# MCU.net
KiCad netlist of a schematic drawn in Altium Designer
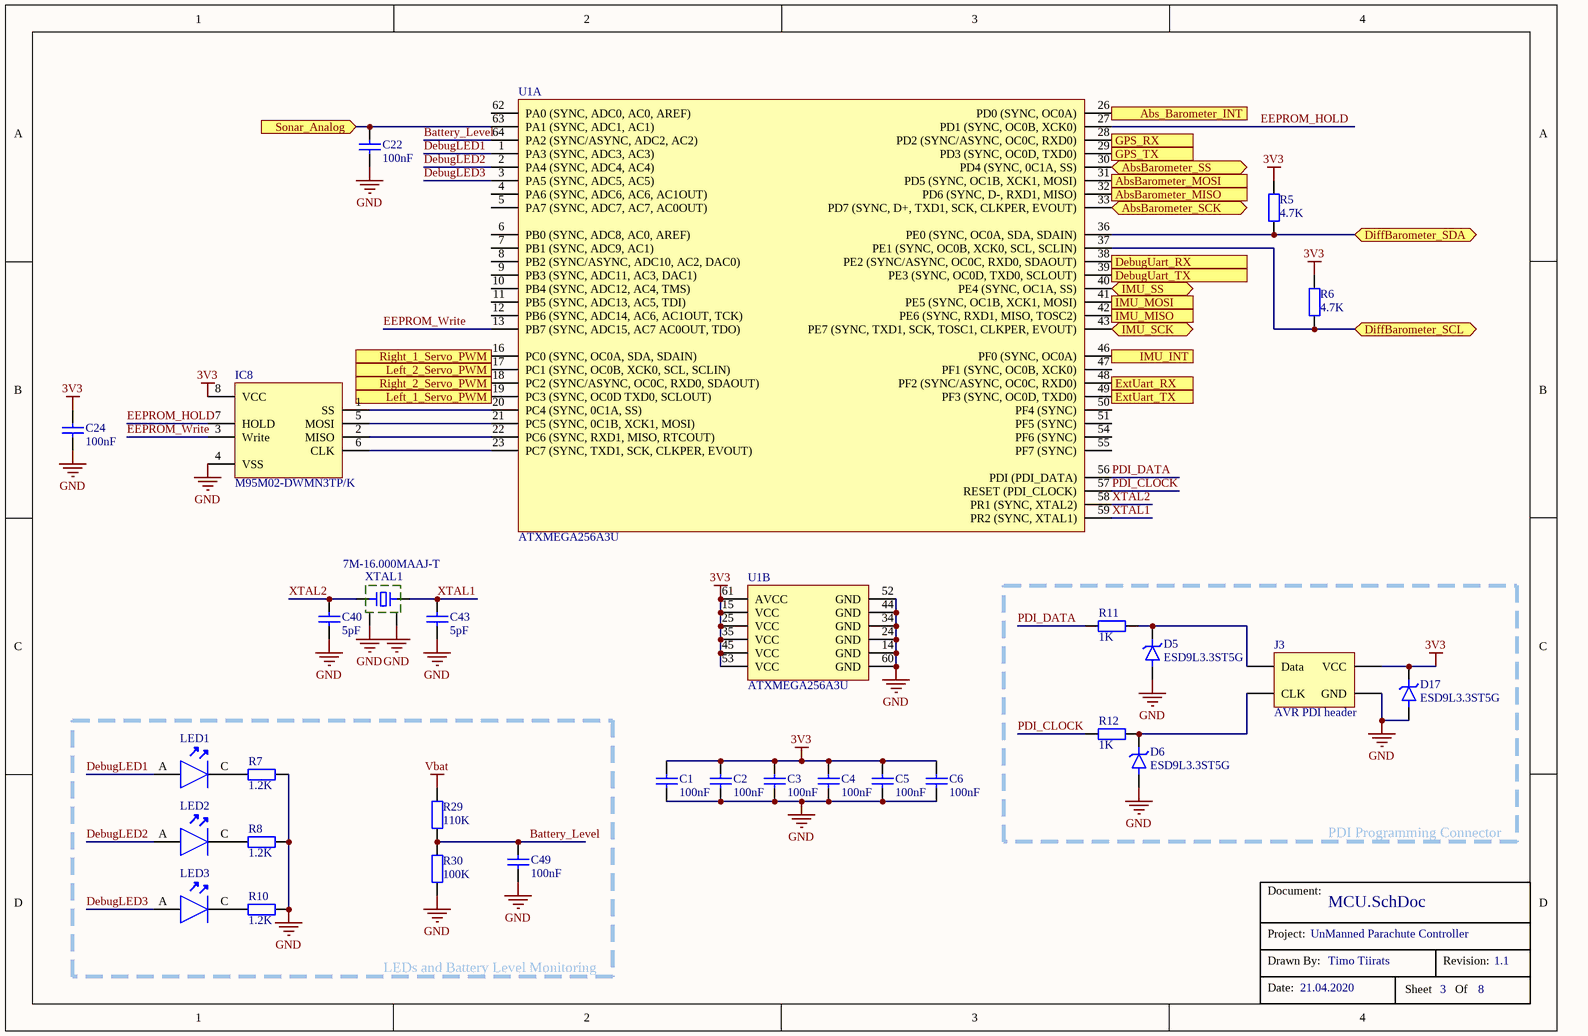
[diagram p0: MCU.SchDoc]

(export (version "E")
  (design (tool "Eeschema 10.0.6"))
  (components
    (comp (ref "C1")
      (value "100nF*V")
      (footprint "C0603 N")
      (description "Ceramic capacitor")
      (fields (field (name "CAPACITANCE") "100nF"))
      (libsource (lib "Passives") (part "Capacitor"))
    )
    (comp (ref "C2")
      (value "100nF*V")
      (footprint "C0603 N")
      (description "Ceramic capacitor")
      (fields (field (name "CAPACITANCE") "100nF"))
      (libsource (lib "Passives") (part "Capacitor"))
    )
    (comp (ref "C3")
      (value "100nF*V")
      (footprint "C0603 N")
      (description "Ceramic capacitor")
      (fields (field (name "CAPACITANCE") "100nF"))
      (libsource (lib "Passives") (part "Capacitor"))
    )
    (comp (ref "C4")
      (value "100nF*V")
      (footprint "C0603 N")
      (description "Ceramic capacitor")
      (fields (field (name "CAPACITANCE") "100nF"))
      (libsource (lib "Passives") (part "Capacitor"))
    )
    (comp (ref "C5")
      (value "100nF*V")
      (footprint "C0603 N")
      (description "Ceramic capacitor")
      (fields (field (name "CAPACITANCE") "100nF"))
      (libsource (lib "Passives") (part "Capacitor"))
    )
    (comp (ref "C6")
      (value "100nF*V")
      (footprint "C0603 N")
      (description "Ceramic capacitor")
      (fields (field (name "CAPACITANCE") "100nF"))
      (libsource (lib "Passives") (part "Capacitor"))
    )
    (comp (ref "C22")
      (value "100nF*V")
      (footprint "C0603 N")
      (description "Ceramic capacitor")
      (fields (field (name "CAPACITANCE") "100nF"))
      (libsource (lib "Passives") (part "Capacitor"))
    )
    (comp (ref "C24")
      (value "100nF*V")
      (footprint "C0603 N")
      (description "Ceramic capacitor")
      (fields (field (name "CAPACITANCE") "100nF"))
      (libsource (lib "Passives") (part "Capacitor"))
    )
    (comp (ref "C40")
      (value "5pF*V")
      (footprint "C0603 N")
      (description "Ceramic capacitor")
      (fields (field (name "CAPACITANCE") "5pF"))
      (libsource (lib "Passives") (part "Capacitor"))
    )
    (comp (ref "C43")
      (value "5pF*V")
      (footprint "C0603 N")
      (description "Ceramic capacitor")
      (fields (field (name "CAPACITANCE") "5pF"))
      (libsource (lib "Passives") (part "Capacitor"))
    )
    (comp (ref "C49")
      (value "100nF*V")
      (footprint "C0603 N")
      (description "Ceramic capacitor")
      (fields (field (name "CAPACITANCE") "100nF"))
      (libsource (lib "Passives") (part "Capacitor"))
    )
    (comp (ref "D5")
      (value "ESD9L3.3ST5G")
      (footprint "SOD923F, NOMINAL")
      (description "TVS DIODE, Unidir, 3.3V/9V, 150mW, SOD-923, ESD9L3.3ST5G, ON SEMICONDUCTOR")
      (fields (field (name "MANUFACTURER") "ON Semiconductor"))
      (libsource (lib "Diodes") (part "ESD9L3.3ST5G"))
    )
    (comp (ref "D6")
      (value "ESD9L3.3ST5G")
      (footprint "SOD923F, NOMINAL")
      (description "TVS DIODE, Unidir, 3.3V/9V, 150mW, SOD-923, ESD9L3.3ST5G, ON SEMICONDUCTOR")
      (fields (field (name "MANUFACTURER") "ON Semiconductor"))
      (libsource (lib "Diodes") (part "ESD9L3.3ST5G"))
    )
    (comp (ref "D17")
      (value "ESD9L3.3ST5G")
      (footprint "SOD923F, NOMINAL")
      (description "TVS DIODE, Unidir, 3.3V/9V, 150mW, SOD-923, ESD9L3.3ST5G, ON SEMICONDUCTOR")
      (fields (field (name "MANUFACTURER") "ON Semiconductor"))
      (libsource (lib "Diodes") (part "ESD9L3.3ST5G"))
    )
    (comp (ref "IC8")
      (value "M95M02-DWMN3TP/K")
      (footprint "SOIC8, JEDEC MS-012-AA, Nominal")
      (description "EEPROM, 2.5...5Vin, 2Mbit, 256Kx8Bit, SPI, 5...10MHz")
      (libsource (lib "Memory") (part "M95M02-DWMN3TP/K"))
    )
    (comp (ref "J3")
      (value "AVR PDI header")
      (footprint "Male 2x3 vertical")
      (description "Male header 2x3, PDI")
      (libsource (lib "pinheader") (part "AVR PDI header 2x3 male"))
    )
    (comp (ref "LED1")
      (value "DebugLED1")
      (footprint "0603 NOMINAL")
      (description "SMD mono-color Chip LED")
      (libsource (lib "LEDs") (part "Generic LED"))
    )
    (comp (ref "LED2")
      (value "DebugLED2")
      (footprint "0603 NOMINAL")
      (description "SMD mono-color Chip LED")
      (libsource (lib "LEDs") (part "Generic LED"))
    )
    (comp (ref "LED3")
      (value "DebugLED3")
      (footprint "0603 NOMINAL")
      (description "SMD mono-color Chip LED")
      (libsource (lib "LEDs") (part "Generic LED"))
    )
    (comp (ref "R5")
      (value "4.7K")
      (footprint "R0603")
      (description "Resistor")
      (fields (field (name "RESISTANCE") "4.7K"))
      (libsource (lib "") (part "Resistor_2"))
    )
    (comp (ref "R6")
      (value "4.7K")
      (footprint "R0603")
      (description "Resistor")
      (fields (field (name "RESISTANCE") "4.7K"))
      (libsource (lib "") (part "Resistor_2"))
    )
    (comp (ref "R7")
      (value "1.2K")
      (footprint "R0603")
      (description "Resistor")
      (fields (field (name "RESISTANCE") "1.2K"))
      (libsource (lib "Passives") (part "Resistor"))
    )
    (comp (ref "R8")
      (value "1.2K")
      (footprint "R0603")
      (description "Resistor")
      (fields (field (name "RESISTANCE") "1.2K"))
      (libsource (lib "Passives") (part "Resistor"))
    )
    (comp (ref "R10")
      (value "1.2K")
      (footprint "R0603")
      (description "Resistor")
      (fields (field (name "RESISTANCE") "1.2K"))
      (libsource (lib "Passives") (part "Resistor"))
    )
    (comp (ref "R11")
      (value "1K")
      (footprint "R0603")
      (description "Resistor")
      (fields (field (name "RESISTANCE") "1K"))
      (libsource (lib "Passives") (part "Resistor"))
    )
    (comp (ref "R12")
      (value "1K")
      (footprint "R0603")
      (description "Resistor")
      (fields (field (name "RESISTANCE") "1K"))
      (libsource (lib "Passives") (part "Resistor"))
    )
    (comp (ref "R29")
      (value "110K")
      (footprint "R0603")
      (description "Resistor")
      (fields (field (name "RESISTANCE") "110K"))
      (libsource (lib "") (part "Resistor_1"))
    )
    (comp (ref "R30")
      (value "100K")
      (footprint "R0603")
      (description "Resistor")
      (fields (field (name "RESISTANCE") "100K"))
      (libsource (lib "") (part "Resistor_1"))
    )
    (comp (ref "U1")
      (value "ATXMEGA256A3U")
      (footprint "TQFP-64, NOMINAL")
      (description "MCU, 8-bit, 256KB flash, 50 I/Os, ATXMEGA2563U, 64-TQFP, Microchip")
      (libsource (lib "AVR") (part "ATXMEGA256A3U"))
    )
    (comp (ref "XTAL1")
      (value "7M-16.000MAAJ-T")
      (footprint "7M 3.2x2.5mm")
      (fields (field (name "MANUFACTURER") "TXC") (field (name "TOLERANCE") "30ppm"))
      (libsource (lib "crystals") (part "7M-16.000MAAJ-T"))
    )
  )
  (nets
    (net (code "1") (name "/AbsBarometer_MISO") (class "Default")
      (node (ref "U1") (pin "32") (pinfunction "PD6_(SYNC,_D-,_RXD1,_MISO)_32") (pintype "passive"))
    )
    (net (code "2") (name "/AbsBarometer_MOSI") (class "Default")
      (node (ref "U1") (pin "31") (pinfunction "PD5_(SYNC,_OC1B,_XCK1,_MOSI)_31") (pintype "passive"))
    )
    (net (code "3") (name "/AbsBarometer_SCK") (class "Default")
      (node (ref "U1") (pin "33") (pinfunction "PD7_(SYNC,_D+,_TXD1,_SCK,_CLKPER,_EVOUT)_33") (pintype "passive"))
    )
    (net (code "4") (name "/AbsBarometer_SS") (class "Default")
      (node (ref "U1") (pin "30") (pinfunction "PD4_(SYNC,_0C1A,_SS)_30") (pintype "passive"))
    )
    (net (code "5") (name "/Abs_Barometer_INT") (class "Default")
      (node (ref "U1") (pin "26") (pinfunction "PD0_(SYNC,_OC0A)_26") (pintype "passive"))
    )
    (net (code "6") (name "/Battery_Level") (class "Default")
      (node (ref "C49") (pin "2") (pinfunction "2_2") (pintype "passive"))
      (node (ref "R29") (pin "2") (pinfunction "2_2") (pintype "passive"))
      (node (ref "R30") (pin "1") (pinfunction "1_1") (pintype "passive"))
      (node (ref "U1") (pin "64") (pinfunction "PA2_(SYNC/ASYNC,_ADC2,_AC2)_64") (pintype "passive"))
    )
    (net (code "7") (name "/DebugLED1") (class "Default")
      (node (ref "LED1") (pin "A") (pinfunction "A_A") (pintype "passive"))
      (node (ref "U1") (pin "1") (pinfunction "PA3_(SYNC,_ADC3,_AC3)_1") (pintype "passive"))
    )
    (net (code "8") (name "/DebugLED2") (class "Default")
      (node (ref "LED2") (pin "A") (pinfunction "A_A") (pintype "passive"))
      (node (ref "U1") (pin "2") (pinfunction "PA4_(SYNC,_ADC4,_AC4)_2") (pintype "passive"))
    )
    (net (code "9") (name "/DebugLED3") (class "Default")
      (node (ref "LED3") (pin "A") (pinfunction "A_A") (pintype "passive"))
      (node (ref "U1") (pin "3") (pinfunction "PA5_(SYNC,_ADC5,_AC5)_3") (pintype "passive"))
    )
    (net (code "10") (name "/DebugUart_RX") (class "Default")
      (node (ref "U1") (pin "38") (pinfunction "PE2_(SYNC/ASYNC,_OC0C,_RXD0,_SDAOUT)_38") (pintype "passive"))
    )
    (net (code "11") (name "/DebugUart_TX") (class "Default")
      (node (ref "U1") (pin "39") (pinfunction "PE3_(SYNC,_OC0D,_TXD0,_SCLOUT)_39") (pintype "passive"))
    )
    (net (code "12") (name "/DiffBarometer_SCL") (class "Default")
      (node (ref "R6") (pin "1") (pinfunction "1_1") (pintype "passive"))
      (node (ref "U1") (pin "37") (pinfunction "PE1_(SYNC,_OC0B,_XCK0,_SCL,_SCLIN)_37") (pintype "passive"))
    )
    (net (code "13") (name "/DiffBarometer_SDA") (class "Default")
      (node (ref "R5") (pin "1") (pinfunction "1_1") (pintype "passive"))
      (node (ref "U1") (pin "36") (pinfunction "PE0_(SYNC,_OC0A,_SDA,_SDAIN)_36") (pintype "passive"))
    )
    (net (code "14") (name "/EEPROM_HOLD") (class "Default")
      (node (ref "IC8") (pin "7") (pinfunction "HOLD_7") (pintype "passive"))
      (node (ref "U1") (pin "27") (pinfunction "PD1_(SYNC,_OC0B,_XCK0)_27") (pintype "passive"))
    )
    (net (code "15") (name "/EEPROM_Write") (class "Default")
      (node (ref "IC8") (pin "3") (pinfunction "Write_3") (pintype "passive"))
      (node (ref "U1") (pin "13") (pinfunction "PB7_(SYNC,_ADC15,_AC7_AC0OUT,_TDO)_13") (pintype "passive"))
    )
    (net (code "16") (name "/ExtUart_RX") (class "Default")
      (node (ref "U1") (pin "48") (pinfunction "PF2_(SYNC/ASYNC,_OC0C,_RXD0)_48") (pintype "passive"))
    )
    (net (code "17") (name "/ExtUart_TX") (class "Default")
      (node (ref "U1") (pin "49") (pinfunction "PF3_(SYNC,_OC0D,_TXD0)_49") (pintype "passive"))
    )
    (net (code "18") (name "/GPS_RX") (class "Default")
      (node (ref "U1") (pin "28") (pinfunction "PD2_(SYNC/ASYNC,_OC0C,_RXD0)_28") (pintype "passive"))
    )
    (net (code "19") (name "/GPS_TX") (class "Default")
      (node (ref "U1") (pin "29") (pinfunction "PD3_(SYNC,_OC0D,_TXD0)_29") (pintype "passive"))
    )
    (net (code "20") (name "/IMU_INT") (class "Default")
      (node (ref "U1") (pin "46") (pinfunction "PF0_(SYNC,_OC0A)_46") (pintype "passive"))
    )
    (net (code "21") (name "/IMU_MISO") (class "Default")
      (node (ref "U1") (pin "42") (pinfunction "PE6_(SYNC,_RXD1,_MISO,_TOSC2)_42") (pintype "passive"))
    )
    (net (code "22") (name "/IMU_MOSI") (class "Default")
      (node (ref "U1") (pin "41") (pinfunction "PE5_(SYNC,_OC1B,_XCK1,_MOSI)_41") (pintype "passive"))
    )
    (net (code "23") (name "/IMU_SCK") (class "Default")
      (node (ref "U1") (pin "43") (pinfunction "PE7_(SYNC,_TXD1,_SCK,_TOSC1,_CLKPER,_EVOUT)_43") (pintype "passive"))
    )
    (net (code "24") (name "/IMU_SS") (class "Default")
      (node (ref "U1") (pin "40") (pinfunction "PE4_(SYNC,_OC1A,_SS)_40") (pintype "passive"))
    )
    (net (code "25") (name "/Left_1_Servo_PWM") (class "Default")
      (node (ref "U1") (pin "19") (pinfunction "PC3_(SYNC,_OC0D_TXD0,_SCLOUT)_19") (pintype "passive"))
    )
    (net (code "26") (name "/Left_2_Servo_PWM") (class "Default")
      (node (ref "U1") (pin "17") (pinfunction "PC1_(SYNC,_OC0B,_XCK0,_SCL,_SCLIN)_17") (pintype "passive"))
    )
    (net (code "27") (name "/PDI_CLOCK") (class "Default")
      (node (ref "R12") (pin "2") (pinfunction "2_2") (pintype "passive"))
      (node (ref "U1") (pin "57") (pinfunction "RESET_(PDI_CLOCK)_57") (pintype "passive"))
    )
    (net (code "28") (name "/PDI_DATA") (class "Default")
      (node (ref "R11") (pin "2") (pinfunction "2_2") (pintype "passive"))
      (node (ref "U1") (pin "56") (pinfunction "PDI_(PDI_DATA)_56") (pintype "passive"))
    )
    (net (code "29") (name "/Right_1_Servo_PWM") (class "Default")
      (node (ref "U1") (pin "16") (pinfunction "PC0_(SYNC,_OC0A,_SDA,_SDAIN)_16") (pintype "passive"))
    )
    (net (code "30") (name "/Right_2_Servo_PWM") (class "Default")
      (node (ref "U1") (pin "18") (pinfunction "PC2_(SYNC/ASYNC,_OC0C,_RXD0,_SDAOUT)_18") (pintype "passive"))
    )
    (net (code "31") (name "/Sonar_Analog") (class "Default")
      (node (ref "C22") (pin "2") (pinfunction "2_2") (pintype "passive"))
      (node (ref "U1") (pin "63") (pinfunction "PA1_(SYNC,_ADC1,_AC1)_63") (pintype "passive"))
    )
    (net (code "32") (name "/XTAL1") (class "Default")
      (node (ref "C43") (pin "2") (pinfunction "2_2") (pintype "passive"))
      (node (ref "U1") (pin "59") (pinfunction "PR2_(SYNC,_XTAL1)_59") (pintype "passive"))
      (node (ref "XTAL1") (pin "3") (pinfunction "X2_3") (pintype "passive"))
    )
    (net (code "33") (name "/XTAL2") (class "Default")
      (node (ref "C40") (pin "2") (pinfunction "2_2") (pintype "passive"))
      (node (ref "U1") (pin "58") (pinfunction "PR1_(SYNC,_XTAL2)_58") (pintype "passive"))
      (node (ref "XTAL1") (pin "1") (pinfunction "X1_1") (pintype "passive"))
    )
    (net (code "34") (name "3V3") (class "Default")
      (node (ref "C1") (pin "2") (pinfunction "2_2") (pintype "passive"))
      (node (ref "C2") (pin "2") (pinfunction "2_2") (pintype "passive"))
      (node (ref "C24") (pin "2") (pinfunction "2_2") (pintype "passive"))
      (node (ref "C3") (pin "2") (pinfunction "2_2") (pintype "passive"))
      (node (ref "C4") (pin "2") (pinfunction "2_2") (pintype "passive"))
      (node (ref "C5") (pin "2") (pinfunction "2_2") (pintype "passive"))
      (node (ref "C6") (pin "2") (pinfunction "2_2") (pintype "passive"))
      (node (ref "D17") (pin "C") (pinfunction "C_C") (pintype "passive"))
      (node (ref "IC8") (pin "8") (pinfunction "VCC_8") (pintype "passive"))
      (node (ref "J3") (pin "2") (pinfunction "VCC_2") (pintype "passive"))
      (node (ref "R5") (pin "2") (pinfunction "2_2") (pintype "passive"))
      (node (ref "R6") (pin "2") (pinfunction "2_2") (pintype "passive"))
      (node (ref "U1") (pin "15") (pinfunction "VCC_15") (pintype "passive"))
      (node (ref "U1") (pin "25") (pinfunction "VCC_25") (pintype "passive"))
      (node (ref "U1") (pin "35") (pinfunction "VCC_35") (pintype "passive"))
      (node (ref "U1") (pin "45") (pinfunction "VCC_45") (pintype "passive"))
      (node (ref "U1") (pin "53") (pinfunction "VCC_53") (pintype "passive"))
      (node (ref "U1") (pin "61") (pinfunction "AVCC_61") (pintype "passive"))
    )
    (net (code "35") (name "GND") (class "Default")
      (node (ref "C1") (pin "1") (pinfunction "1_1") (pintype "passive"))
      (node (ref "C2") (pin "1") (pinfunction "1_1") (pintype "passive"))
      (node (ref "C22") (pin "1") (pinfunction "1_1") (pintype "passive"))
      (node (ref "C24") (pin "1") (pinfunction "1_1") (pintype "passive"))
      (node (ref "C3") (pin "1") (pinfunction "1_1") (pintype "passive"))
      (node (ref "C4") (pin "1") (pinfunction "1_1") (pintype "passive"))
      (node (ref "C40") (pin "1") (pinfunction "1_1") (pintype "passive"))
      (node (ref "C43") (pin "1") (pinfunction "1_1") (pintype "passive"))
      (node (ref "C49") (pin "1") (pinfunction "1_1") (pintype "passive"))
      (node (ref "C5") (pin "1") (pinfunction "1_1") (pintype "passive"))
      (node (ref "C6") (pin "1") (pinfunction "1_1") (pintype "passive"))
      (node (ref "D17") (pin "A") (pinfunction "A_A") (pintype "passive"))
      (node (ref "D5") (pin "A") (pinfunction "A_A") (pintype "passive"))
      (node (ref "D6") (pin "A") (pinfunction "A_A") (pintype "passive"))
      (node (ref "IC8") (pin "4") (pinfunction "VSS_4") (pintype "passive"))
      (node (ref "J3") (pin "6") (pinfunction "GND_6") (pintype "passive"))
      (node (ref "R10") (pin "1") (pinfunction "1_1") (pintype "passive"))
      (node (ref "R30") (pin "2") (pinfunction "2_2") (pintype "passive"))
      (node (ref "R7") (pin "1") (pinfunction "1_1") (pintype "passive"))
      (node (ref "R8") (pin "1") (pinfunction "1_1") (pintype "passive"))
      (node (ref "U1") (pin "14") (pinfunction "GND_14") (pintype "passive"))
      (node (ref "U1") (pin "24") (pinfunction "GND_24") (pintype "passive"))
      (node (ref "U1") (pin "34") (pinfunction "GND_34") (pintype "passive"))
      (node (ref "U1") (pin "44") (pinfunction "GND_44") (pintype "passive"))
      (node (ref "U1") (pin "52") (pinfunction "GND_52") (pintype "passive"))
      (node (ref "U1") (pin "60") (pinfunction "GND_60") (pintype "passive"))
      (node (ref "XTAL1") (pin "2") (pinfunction "gnd_2") (pintype "passive"))
      (node (ref "XTAL1") (pin "4") (pinfunction "gnd1_4") (pintype "passive"))
    )
    (net (code "36") (name "Net-(IC8-CLK)") (class "Default")
      (node (ref "IC8") (pin "6") (pinfunction "CLK_6") (pintype "passive"))
      (node (ref "U1") (pin "23") (pinfunction "PC7_(SYNC,_TXD1,_SCK,_CLKPER,_EVOUT)_23") (pintype "passive"))
    )
    (net (code "37") (name "Net-(IC8-MISO)") (class "Default")
      (node (ref "IC8") (pin "2") (pinfunction "MISO_2") (pintype "passive"))
      (node (ref "U1") (pin "22") (pinfunction "PC6_(SYNC,_RXD1,_MISO,_RTCOUT)_22") (pintype "passive"))
    )
    (net (code "38") (name "Net-(IC8-MOSI)") (class "Default")
      (node (ref "IC8") (pin "5") (pinfunction "MOSI_5") (pintype "passive"))
      (node (ref "U1") (pin "21") (pinfunction "PC5_(SYNC,_0C1B,_XCK1,_MOSI)_21") (pintype "passive"))
    )
    (net (code "39") (name "Net-(IC8-SS)") (class "Default")
      (node (ref "IC8") (pin "1") (pinfunction "SS_1") (pintype "passive"))
      (node (ref "U1") (pin "20") (pinfunction "PC4_(SYNC,_0C1A,_SS)_20") (pintype "passive"))
    )
    (net (code "40") (name "Net-(J3-CLK)") (class "Default")
      (node (ref "D6") (pin "C") (pinfunction "C_C") (pintype "passive"))
      (node (ref "J3") (pin "5") (pinfunction "CLK_5") (pintype "passive"))
      (node (ref "R12") (pin "1") (pinfunction "1_1") (pintype "passive"))
    )
    (net (code "41") (name "Net-(J3-Data)") (class "Default")
      (node (ref "D5") (pin "C") (pinfunction "C_C") (pintype "passive"))
      (node (ref "J3") (pin "1") (pinfunction "Data_1") (pintype "passive"))
      (node (ref "R11") (pin "1") (pinfunction "1_1") (pintype "passive"))
    )
    (net (code "42") (name "Net-(LED1-PadC)") (class "Default")
      (node (ref "LED1") (pin "C") (pinfunction "C_C") (pintype "passive"))
      (node (ref "R7") (pin "2") (pinfunction "2_2") (pintype "passive"))
    )
    (net (code "43") (name "Net-(LED2-PadC)") (class "Default")
      (node (ref "LED2") (pin "C") (pinfunction "C_C") (pintype "passive"))
      (node (ref "R8") (pin "2") (pinfunction "2_2") (pintype "passive"))
    )
    (net (code "44") (name "Net-(LED3-PadC)") (class "Default")
      (node (ref "LED3") (pin "C") (pinfunction "C_C") (pintype "passive"))
      (node (ref "R10") (pin "2") (pinfunction "2_2") (pintype "passive"))
    )
    (net (code "45") (name "Vbat") (class "Default")
      (node (ref "R29") (pin "1") (pinfunction "1_1") (pintype "passive"))
    )
    (net (code "46") (name "unconnected-(U1A-PA0_(SYNC,_ADC0,_AC0,_AREF)-Pad62)") (class "Default")
      (node (ref "U1") (pin "62") (pinfunction "PA0_(SYNC,_ADC0,_AC0,_AREF)_62") (pintype "passive"))
    )
    (net (code "47") (name "unconnected-(U1A-PA6_(SYNC,_ADC6,_AC6,_AC1OUT)-Pad4)") (class "Default")
      (node (ref "U1") (pin "4") (pinfunction "PA6_(SYNC,_ADC6,_AC6,_AC1OUT)_4") (pintype "passive"))
    )
    (net (code "48") (name "unconnected-(U1A-PA7_(SYNC,_ADC7,_AC7,_AC0OUT)-Pad5)") (class "Default")
      (node (ref "U1") (pin "5") (pinfunction "PA7_(SYNC,_ADC7,_AC7,_AC0OUT)_5") (pintype "passive"))
    )
    (net (code "49") (name "unconnected-(U1A-PB0_(SYNC,_ADC8,_AC0,_AREF)-Pad6)") (class "Default")
      (node (ref "U1") (pin "6") (pinfunction "PB0_(SYNC,_ADC8,_AC0,_AREF)_6") (pintype "passive"))
    )
    (net (code "50") (name "unconnected-(U1A-PB1_(SYNC,_ADC9,_AC1)-Pad7)") (class "Default")
      (node (ref "U1") (pin "7") (pinfunction "PB1_(SYNC,_ADC9,_AC1)_7") (pintype "passive"))
    )
    (net (code "51") (name "unconnected-(U1A-PB2_(SYNC{slash}ASYNC,_ADC10,_AC2,_DAC0)-Pad8)") (class "Default")
      (node (ref "U1") (pin "8") (pinfunction "PB2_(SYNC/ASYNC,_ADC10,_AC2,_DAC0)_8") (pintype "passive"))
    )
    (net (code "52") (name "unconnected-(U1A-PB3_(SYNC,_ADC11,_AC3,_DAC1)-Pad9)") (class "Default")
      (node (ref "U1") (pin "9") (pinfunction "PB3_(SYNC,_ADC11,_AC3,_DAC1)_9") (pintype "passive"))
    )
    (net (code "53") (name "unconnected-(U1A-PB4_(SYNC,_ADC12,_AC4,_TMS)-Pad10)") (class "Default")
      (node (ref "U1") (pin "10") (pinfunction "PB4_(SYNC,_ADC12,_AC4,_TMS)_10") (pintype "passive"))
    )
    (net (code "54") (name "unconnected-(U1A-PB5_(SYNC,_ADC13,_AC5,_TDI)-Pad11)") (class "Default")
      (node (ref "U1") (pin "11") (pinfunction "PB5_(SYNC,_ADC13,_AC5,_TDI)_11") (pintype "passive"))
    )
    (net (code "55") (name "unconnected-(U1A-PB6_(SYNC,_ADC14,_AC6,_AC1OUT,_TCK)-Pad12)") (class "Default")
      (node (ref "U1") (pin "12") (pinfunction "PB6_(SYNC,_ADC14,_AC6,_AC1OUT,_TCK)_12") (pintype "passive"))
    )
    (net (code "56") (name "unconnected-(U1A-PF1_(SYNC,_OC0B,_XCK0)-Pad47)") (class "Default")
      (node (ref "U1") (pin "47") (pinfunction "PF1_(SYNC,_OC0B,_XCK0)_47") (pintype "passive"))
    )
    (net (code "57") (name "unconnected-(U1A-PF4_(SYNC)-Pad50)") (class "Default")
      (node (ref "U1") (pin "50") (pinfunction "PF4_(SYNC)_50") (pintype "passive"))
    )
    (net (code "58") (name "unconnected-(U1A-PF5_(SYNC)-Pad51)") (class "Default")
      (node (ref "U1") (pin "51") (pinfunction "PF5_(SYNC)_51") (pintype "passive"))
    )
    (net (code "59") (name "unconnected-(U1A-PF6_(SYNC)-Pad54)") (class "Default")
      (node (ref "U1") (pin "54") (pinfunction "PF6_(SYNC)_54") (pintype "passive"))
    )
    (net (code "60") (name "unconnected-(U1A-PF7_(SYNC)-Pad55)") (class "Default")
      (node (ref "U1") (pin "55") (pinfunction "PF7_(SYNC)_55") (pintype "passive"))
    )
  )
)
